# 01-POWER-FILTER.net
KiCad netlist of a schematic drawn in Altium Designer
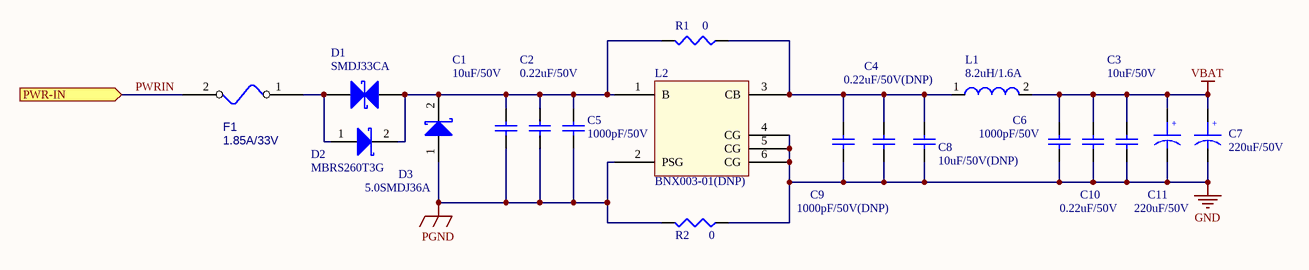
[diagram p0: 01-POWER-FILTER.SchDoc]

(export (version "E")
  (design (tool "Eeschema 10.0.6"))
  (components
    (comp (ref "C1")
      (value "10uF/50V")
      (footprint "1210")
      (description "Capacitor")
      (fields (field (name "PUBLISHER") "Altium Limited"))
      (libsource (lib "Miscellaneous Devices") (part "Cap"))
    )
    (comp (ref "C2")
      (value "0.22uF/50V")
      (footprint "0603")
      (description "Capacitor")
      (fields (field (name "PUBLISHER") "Altium Limited"))
      (libsource (lib "Miscellaneous Devices") (part "Cap"))
    )
    (comp (ref "C3")
      (value "10uF/50V")
      (footprint "1210")
      (description "Capacitor")
      (fields (field (name "PUBLISHER") "Altium Limited"))
      (libsource (lib "Miscellaneous Devices") (part "Cap"))
    )
    (comp (ref "C4")
      (value "0.22uF/50V(DNP)")
      (footprint "0603")
      (description "Capacitor")
      (fields (field (name "PUBLISHER") "Altium Limited"))
      (libsource (lib "Miscellaneous Devices") (part "Cap"))
    )
    (comp (ref "C5")
      (value "1000pF/50V")
      (footprint "0402")
      (description "Capacitor")
      (fields (field (name "PUBLISHER") "Altium Limited"))
      (libsource (lib "Miscellaneous Devices") (part "Cap"))
    )
    (comp (ref "C6")
      (value "1000pF/50V")
      (footprint "0402")
      (description "Capacitor")
      (fields (field (name "PUBLISHER") "Altium Limited"))
      (libsource (lib "") (part "Cap_1"))
    )
    (comp (ref "C7") (value "220uF/50V") (footprint "DL-10*10.5") (libsource (lib "*") (part "CAP WP")))
    (comp (ref "C8")
      (value "10uF/50V(DNP)")
      (footprint "1210")
      (description "Capacitor")
      (fields (field (name "PUBLISHER") "Altium Limited"))
      (libsource (lib "Miscellaneous Devices") (part "Cap"))
    )
    (comp (ref "C9")
      (value "1000pF/50V(DNP)")
      (footprint "0402")
      (description "Capacitor")
      (fields (field (name "PUBLISHER") "Altium Limited"))
      (libsource (lib "Miscellaneous Devices") (part "Cap"))
    )
    (comp (ref "C10")
      (value "0.22uF/50V")
      (footprint "0603")
      (description "Capacitor")
      (fields (field (name "PUBLISHER") "Altium Limited"))
      (libsource (lib "Miscellaneous Devices") (part "Cap"))
    )
    (comp (ref "C11") (value "220uF/50V") (footprint "DL-10*10.5") (libsource (lib "*") (part "CAP WP")))
    (comp (ref "D1") (value "SMDJ33CA") (footprint "SMC") (libsource (lib "Schlib") (part "TVS-BI")))
    (comp (ref "D2")
      (value "MBRS260T3G")
      (footprint "SMB")
      (description "Schottky Rectifier")
      (libsource (lib "Miscellaneous Devices") (part "Diode 11DQ03"))
    )
    (comp (ref "D3")
      (value "5.0SMDJ36A")
      (footprint "SMC")
      (description "Schottky Rectifier")
      (libsource (lib "Miscellaneous Devices") (part "Diode 11DQ03"))
    )
    (comp (ref "F1") (value "1.85A/33V") (footprint "2920") (libsource (lib "*") (part "2A_32VDC_0467-002")))
    (comp (ref "L1")
      (value "8.2uH/1.6A")
      (footprint "IND-SMD-5.8*5.8")
      (fields (field (name "PART NUMBER") "SH00000AJ00"))
      (libsource (lib "*") (part "4.7UH_CDH2D09BNP-4R7MC_0.7A_20%"))
    )
    (comp (ref "L2")
      (value "BNX003-01(DNP)")
      (footprint "BNX002-001")
      (libsource (lib "Schlib") (part "BNX002-01"))
    )
    (comp (ref "R1")
      (value "0")
      (footprint "1812")
      (description "Resistor")
      (fields (field (name "PUBLISHER") "Altium Limited"))
      (libsource (lib "Miscellaneous Devices") (part "Res3"))
    )
    (comp (ref "R2")
      (value "0")
      (footprint "1812")
      (description "Resistor")
      (fields (field (name "PUBLISHER") "Altium Limited"))
      (libsource (lib "Miscellaneous Devices") (part "Res3"))
    )
  )
  (nets
    (net (code "1") (name "/PWRIN") (class "Default")
      (node (ref "F1") (pin "2") (pinfunction "2_2") (pintype "passive"))
    )
    (net (code "2") (name "GND") (class "Default")
      (node (ref "C10") (pin "2") (pinfunction "2_2") (pintype "passive"))
      (node (ref "C11") (pin "2") (pinfunction "2_2") (pintype "passive"))
      (node (ref "C3") (pin "2") (pinfunction "2_2") (pintype "passive"))
      (node (ref "C4") (pin "2") (pinfunction "2_2") (pintype "passive"))
      (node (ref "C6") (pin "2") (pinfunction "2_2") (pintype "passive"))
      (node (ref "C7") (pin "2") (pinfunction "2_2") (pintype "passive"))
      (node (ref "C8") (pin "2") (pinfunction "2_2") (pintype "passive"))
      (node (ref "C9") (pin "2") (pinfunction "2_2") (pintype "passive"))
      (node (ref "L2") (pin "4") (pinfunction "CG_4") (pintype "passive"))
      (node (ref "L2") (pin "5") (pinfunction "CG_5") (pintype "passive"))
      (node (ref "L2") (pin "6") (pinfunction "CG_6") (pintype "passive"))
      (node (ref "R2") (pin "1") (pinfunction "1_1") (pintype "passive"))
    )
    (net (code "3") (name "Net-(D2-A)") (class "Default")
      (node (ref "D1") (pin "1") (pinfunction "1_1") (pintype "passive"))
      (node (ref "D2") (pin "1") (pinfunction "A_1") (pintype "passive"))
      (node (ref "F1") (pin "1") (pinfunction "1_1") (pintype "passive"))
    )
    (net (code "4") (name "Net-(D2-K)") (class "Default")
      (node (ref "C1") (pin "1") (pinfunction "1_1") (pintype "passive"))
      (node (ref "C2") (pin "1") (pinfunction "1_1") (pintype "passive"))
      (node (ref "C5") (pin "1") (pinfunction "1_1") (pintype "passive"))
      (node (ref "D1") (pin "2") (pinfunction "2_2") (pintype "passive"))
      (node (ref "D2") (pin "2") (pinfunction "K_2") (pintype "passive"))
      (node (ref "D3") (pin "2") (pinfunction "K_2") (pintype "passive"))
      (node (ref "L2") (pin "1") (pinfunction "B_1") (pintype "passive"))
      (node (ref "R1") (pin "2") (pinfunction "2_2") (pintype "passive"))
    )
    (net (code "5") (name "Net-(L2-CB)") (class "Default")
      (node (ref "C4") (pin "1") (pinfunction "1_1") (pintype "passive"))
      (node (ref "C8") (pin "1") (pinfunction "1_1") (pintype "passive"))
      (node (ref "C9") (pin "1") (pinfunction "1_1") (pintype "passive"))
      (node (ref "L1") (pin "1") (pinfunction "1_1") (pintype "passive"))
      (node (ref "L2") (pin "3") (pinfunction "CB_3") (pintype "passive"))
      (node (ref "R1") (pin "1") (pinfunction "1_1") (pintype "passive"))
    )
    (net (code "6") (name "PGND") (class "Default")
      (node (ref "C1") (pin "2") (pinfunction "2_2") (pintype "passive"))
      (node (ref "C2") (pin "2") (pinfunction "2_2") (pintype "passive"))
      (node (ref "C5") (pin "2") (pinfunction "2_2") (pintype "passive"))
      (node (ref "D3") (pin "1") (pinfunction "A_1") (pintype "passive"))
      (node (ref "L2") (pin "2") (pinfunction "PSG_2") (pintype "passive"))
      (node (ref "R2") (pin "2") (pinfunction "2_2") (pintype "passive"))
    )
    (net (code "7") (name "VBAT") (class "Default")
      (node (ref "C10") (pin "1") (pinfunction "1_1") (pintype "passive"))
      (node (ref "C11") (pin "1") (pinfunction "1_1") (pintype "passive"))
      (node (ref "C3") (pin "1") (pinfunction "1_1") (pintype "passive"))
      (node (ref "C6") (pin "1") (pinfunction "1_1") (pintype "passive"))
      (node (ref "C7") (pin "1") (pinfunction "1_1") (pintype "passive"))
      (node (ref "L1") (pin "2") (pinfunction "2_2") (pintype "passive"))
    )
  )
)
